# coolaz-sheet.net
KiCad netlist of a schematic drawn in Altium Designer
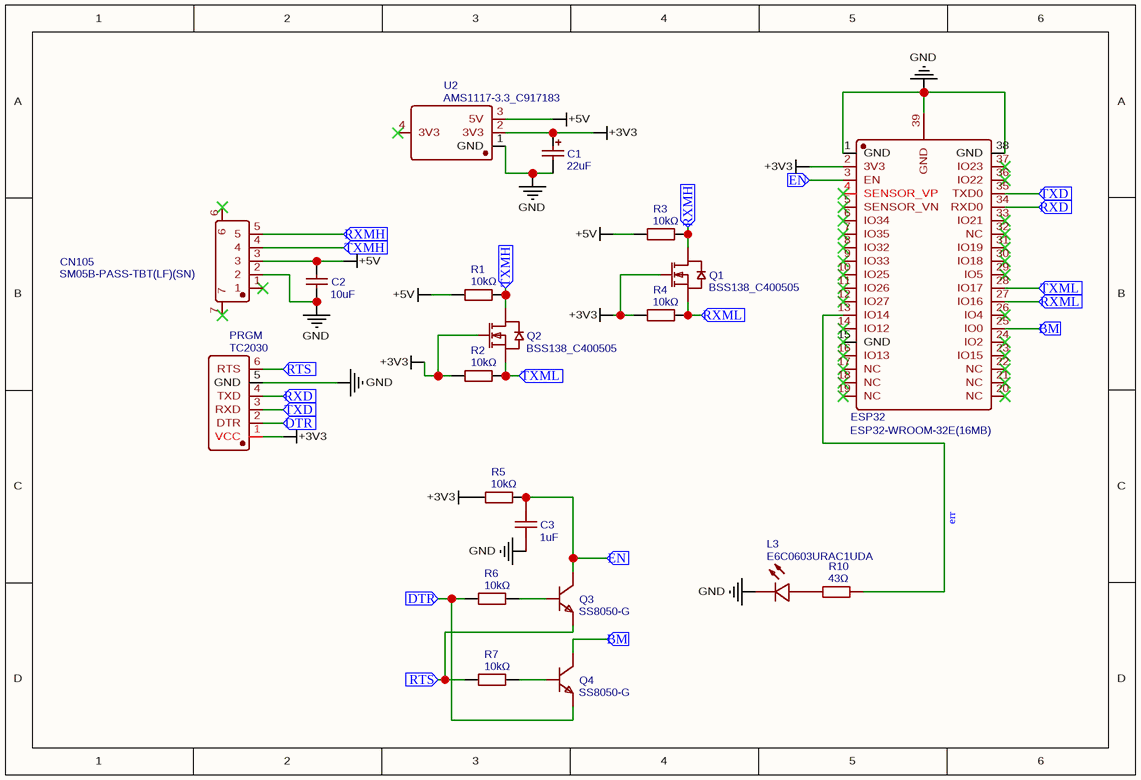
[diagram p0: coolaz-sheet.schdoc]

(export (version "E")
  (design (tool "Eeschema 10.0.6"))
  (components
    (comp (ref "C1")
      (value "22uF")
      (fields
        (field (name "BOM_MANUFACTURER PART") "CA45-B-16V-22UF-K")
        (field (name "BOM_SUPPLIER PART") "C129568")
      )
      (libsource (lib "altium-import") (part "root_1_22uF_"))
    )
    (comp (ref "C2")
      (value "10uF")
      (fields
        (field (name "BOM_MANUFACTURER PART") "CL05A106MQ5NUNC")
        (field (name "BOM_SUPPLIER PART") "C15525")
      )
      (libsource (lib "altium-import") (part "root_1_10uF_"))
    )
    (comp (ref "C3")
      (value "1uF")
      (fields
        (field (name "BOM_MANUFACTURER PART") "CL05A105KA5NQNC")
        (field (name "BOM_SUPPLIER PART") "C52923")
      )
      (libsource (lib "altium-import") (part "root_1_1uF_"))
    )
    (comp (ref "CN105")
      (value "SM05B-PASS-TBT(LF)(SN)")
      (fields (field (name "BOM_SUPPLIER PART") "C485350") (field (name "CONTRIBUTOR") "LCSC"))
      (libsource (lib "altium-import") (part "root_2_SM05B-PASS-TBT(LF)(SN)_"))
    )
    (comp (ref "ESP32")
      (value "ESP32-WROOM-32E(16MB)")
      (fields (field (name "BOM_SUPPLIER PART") "C701343") (field (name "CONTRIBUTOR") "LCSC"))
      (libsource (lib "altium-import") (part "root_0_ESP32-WROOM-32E(16MB)_"))
    )
    (comp (ref "L3")
      (value "E6C0603URAC1UDA")
      (fields (field (name "BOM_SUPPLIER PART") "C375444") (field (name "CONTRIBUTOR") "LCSC"))
      (libsource (lib "altium-import") (part "root_0_E6C0603URAC1UDA_"))
    )
    (comp (ref "PRGM")
      (value "TC2030")
      (fields
        (field (name "BOM_MANUFACTURER PART") "TC2030-FTDI-C232HD-DDHSP-0-DTR")
        (field (name "CONTRIBUTOR") "thomas_1863")
      )
      (libsource (lib "altium-import") (part "root_2_TC2030_"))
    )
    (comp (ref "Q1")
      (value "BSS138_C400505")
      (fields
        (field (name "BOM_SUPPLIER PART") "C400505")
        (field (name "BOM_MANUFACTURER PART") "BSS138")
        (field (name "CONTRIBUTOR") "LCSC")
      )
      (libsource (lib "altium-import") (part "root_0_BSS138_C400505_"))
    )
    (comp (ref "Q2")
      (value "BSS138_C400505")
      (fields
        (field (name "BOM_SUPPLIER PART") "C400505")
        (field (name "BOM_MANUFACTURER PART") "BSS138")
        (field (name "CONTRIBUTOR") "LCSC")
      )
      (libsource (lib "altium-import") (part "root_0_BSS138_C400505_"))
    )
    (comp (ref "Q3")
      (value "SS8050-G")
      (fields (field (name "BOM_SUPPLIER PART") "C164886") (field (name "CONTRIBUTOR") "LCSC"))
      (libsource (lib "altium-import") (part "root_0_SS8050-G_"))
    )
    (comp (ref "Q4")
      (value "SS8050-G")
      (fields (field (name "BOM_SUPPLIER PART") "C164886") (field (name "CONTRIBUTOR") "LCSC"))
      (libsource (lib "altium-import") (part "root_0_SS8050-G_"))
    )
    (comp (ref "R1")
      (value "10kΩ")
      (fields
        (field (name "BOM_MANUFACTURER PART") "0603WAF1002T5E")
        (field (name "BOM_SUPPLIER PART") "C25804")
      )
      (libsource (lib "altium-import") (part "root_0_10kΩ_"))
    )
    (comp (ref "R2")
      (value "10kΩ")
      (fields
        (field (name "BOM_MANUFACTURER PART") "0603WAF1002T5E")
        (field (name "BOM_SUPPLIER PART") "C25804")
      )
      (libsource (lib "altium-import") (part "root_0_10kΩ_"))
    )
    (comp (ref "R3")
      (value "10kΩ")
      (fields
        (field (name "BOM_MANUFACTURER PART") "0603WAF1002T5E")
        (field (name "BOM_SUPPLIER PART") "C25804")
      )
      (libsource (lib "altium-import") (part "root_0_10kΩ_"))
    )
    (comp (ref "R4")
      (value "10kΩ")
      (fields
        (field (name "BOM_MANUFACTURER PART") "0603WAF1002T5E")
        (field (name "BOM_SUPPLIER PART") "C25804")
      )
      (libsource (lib "altium-import") (part "root_0_10kΩ_"))
    )
    (comp (ref "R5")
      (value "10kΩ")
      (fields
        (field (name "BOM_MANUFACTURER PART") "0603WAF1002T5E")
        (field (name "BOM_SUPPLIER PART") "C25804")
      )
      (libsource (lib "altium-import") (part "root_0_10kΩ_"))
    )
    (comp (ref "R6")
      (value "10kΩ")
      (fields
        (field (name "BOM_MANUFACTURER PART") "0603WAF1002T5E")
        (field (name "BOM_SUPPLIER PART") "C25804")
      )
      (libsource (lib "altium-import") (part "root_0_10kΩ_"))
    )
    (comp (ref "R7")
      (value "10kΩ")
      (fields
        (field (name "BOM_MANUFACTURER PART") "0603WAF1002T5E")
        (field (name "BOM_SUPPLIER PART") "C25804")
      )
      (libsource (lib "altium-import") (part "root_0_10kΩ_"))
    )
    (comp (ref "R10")
      (value "43Ω")
      (fields
        (field (name "BOM_SUPPLIER PART") "C270600")
        (field (name "BOM_MANUFACTURER PART") "0402WGF430JTCE")
        (field (name "CONTRIBUTOR") "LCSC")
      )
      (libsource (lib "altium-import") (part "root_0_43Ω_"))
    )
    (comp (ref "U2")
      (value "AMS1117-3.3_C917183")
      (fields
        (field (name "BOM_SUPPLIER PART") "C917183")
        (field (name "BOM_MANUFACTURER PART") "AMS1117-3.3")
        (field (name "CONTRIBUTOR") "LCSC")
      )
      (libsource (lib "altium-import") (part "root_2_AMS1117-3.3_C917183_"))
    )
  )
  (nets
    (net (code "1") (name "+3V3") (class "Default")
      (node (ref "C1") (pin "1") (pinfunction "1_1") (pintype "passive"))
      (node (ref "ESP32") (pin "2") (pinfunction "3V3_2") (pintype "passive"))
      (node (ref "PRGM") (pin "1") (pinfunction "VCC_1") (pintype "passive"))
      (node (ref "Q1") (pin "1") (pinfunction "G_1") (pintype "passive"))
      (node (ref "Q2") (pin "1") (pinfunction "G_1") (pintype "passive"))
      (node (ref "R2") (pin "1") (pinfunction "1_1") (pintype "passive"))
      (node (ref "R4") (pin "1") (pinfunction "1_1") (pintype "passive"))
      (node (ref "R5") (pin "1") (pinfunction "1_1") (pintype "passive"))
      (node (ref "U2") (pin "2") (pinfunction "3V3_2") (pintype "passive"))
    )
    (net (code "2") (name "+5V") (class "Default")
      (node (ref "C2") (pin "2") (pinfunction "2_2") (pintype "passive"))
      (node (ref "CN105") (pin "3") (pinfunction "3_3") (pintype "passive"))
      (node (ref "R1") (pin "1") (pinfunction "1_1") (pintype "passive"))
      (node (ref "R3") (pin "1") (pinfunction "1_1") (pintype "passive"))
      (node (ref "U2") (pin "3") (pinfunction "5V_3") (pintype "passive"))
    )
    (net (code "3") (name "/BM") (class "Default")
      (node (ref "ESP32") (pin "25") (pinfunction "IO0_25") (pintype "passive"))
      (node (ref "Q4") (pin "3") (pinfunction "C_3") (pintype "passive"))
    )
    (net (code "4") (name "/DTR") (class "Default")
      (node (ref "PRGM") (pin "2") (pinfunction "DTR_2") (pintype "passive"))
      (node (ref "Q4") (pin "2") (pinfunction "E_2") (pintype "passive"))
      (node (ref "R6") (pin "1") (pinfunction "1_1") (pintype "passive"))
    )
    (net (code "5") (name "/EN") (class "Default")
      (node (ref "C3") (pin "2") (pinfunction "2_2") (pintype "passive"))
      (node (ref "ESP32") (pin "3") (pinfunction "EN_3") (pintype "passive"))
      (node (ref "Q3") (pin "3") (pinfunction "C_3") (pintype "passive"))
      (node (ref "R5") (pin "2") (pinfunction "2_2") (pintype "passive"))
    )
    (net (code "6") (name "/RTS") (class "Default")
      (node (ref "PRGM") (pin "6") (pinfunction "RTS_6") (pintype "passive"))
      (node (ref "Q3") (pin "2") (pinfunction "E_2") (pintype "passive"))
      (node (ref "R7") (pin "1") (pinfunction "1_1") (pintype "passive"))
    )
    (net (code "7") (name "/RXD") (class "Default")
      (node (ref "ESP32") (pin "34") (pinfunction "RXD0_34") (pintype "passive"))
      (node (ref "PRGM") (pin "4") (pinfunction "TXD_4") (pintype "passive"))
    )
    (net (code "8") (name "/RXMH") (class "Default")
      (node (ref "CN105") (pin "5") (pinfunction "5_5") (pintype "passive"))
      (node (ref "Q1") (pin "3") (pinfunction "D_3") (pintype "passive"))
      (node (ref "R3") (pin "2") (pinfunction "2_2") (pintype "passive"))
    )
    (net (code "9") (name "/RXML") (class "Default")
      (node (ref "ESP32") (pin "27") (pinfunction "IO16_27") (pintype "passive"))
      (node (ref "Q1") (pin "2") (pinfunction "S_2") (pintype "passive"))
      (node (ref "R4") (pin "2") (pinfunction "2_2") (pintype "passive"))
    )
    (net (code "10") (name "/TXD") (class "Default")
      (node (ref "ESP32") (pin "35") (pinfunction "TXD0_35") (pintype "passive"))
      (node (ref "PRGM") (pin "3") (pinfunction "RXD_3") (pintype "passive"))
    )
    (net (code "11") (name "/TXMH") (class "Default")
      (node (ref "CN105") (pin "4") (pinfunction "4_4") (pintype "passive"))
      (node (ref "Q2") (pin "3") (pinfunction "D_3") (pintype "passive"))
      (node (ref "R1") (pin "2") (pinfunction "2_2") (pintype "passive"))
    )
    (net (code "12") (name "/TXML") (class "Default")
      (node (ref "ESP32") (pin "28") (pinfunction "IO17_28") (pintype "passive"))
      (node (ref "Q2") (pin "2") (pinfunction "S_2") (pintype "passive"))
      (node (ref "R2") (pin "2") (pinfunction "2_2") (pintype "passive"))
    )
    (net (code "13") (name "/err") (class "Default")
      (node (ref "ESP32") (pin "13") (pinfunction "IO14_13") (pintype "passive"))
      (node (ref "R10") (pin "2") (pinfunction "2_2") (pintype "passive"))
    )
    (net (code "14") (name "GND") (class "Default")
      (node (ref "C1") (pin "2") (pinfunction "2_2") (pintype "passive"))
      (node (ref "C2") (pin "1") (pinfunction "1_1") (pintype "passive"))
      (node (ref "C3") (pin "1") (pinfunction "1_1") (pintype "passive"))
      (node (ref "CN105") (pin "2") (pinfunction "2_2") (pintype "passive"))
      (node (ref "ESP32") (pin "1") (pinfunction "GND_1") (pintype "passive"))
      (node (ref "ESP32") (pin "38") (pinfunction "GND_38") (pintype "passive"))
      (node (ref "ESP32") (pin "39") (pinfunction "GND_39") (pintype "passive"))
      (node (ref "L3") (pin "2") (pinfunction "-_2") (pintype "passive"))
      (node (ref "PRGM") (pin "5") (pinfunction "GND_5") (pintype "passive"))
      (node (ref "U2") (pin "1") (pinfunction "GND_1") (pintype "passive"))
    )
    (net (code "15") (name "Net-(L3-+)") (class "Default")
      (node (ref "L3") (pin "1") (pinfunction "+_1") (pintype "passive"))
      (node (ref "R10") (pin "1") (pinfunction "1_1") (pintype "passive"))
    )
    (net (code "16") (name "Net-(Q3-B)") (class "Default")
      (node (ref "Q3") (pin "1") (pinfunction "B_1") (pintype "passive"))
      (node (ref "R6") (pin "2") (pinfunction "2_2") (pintype "passive"))
    )
    (net (code "17") (name "Net-(Q4-B)") (class "Default")
      (node (ref "Q4") (pin "1") (pinfunction "B_1") (pintype "passive"))
      (node (ref "R7") (pin "2") (pinfunction "2_2") (pintype "passive"))
    )
    (net (code "18") (name "unconnected-(CN105-Pad1)") (class "Default")
      (node (ref "CN105") (pin "1") (pinfunction "1_1") (pintype "passive+no_connect"))
    )
    (net (code "19") (name "unconnected-(CN105-Pad6)") (class "Default")
      (node (ref "CN105") (pin "6") (pinfunction "6_6") (pintype "passive+no_connect"))
    )
    (net (code "20") (name "unconnected-(CN105-Pad7)") (class "Default")
      (node (ref "CN105") (pin "7") (pinfunction "7_7") (pintype "passive+no_connect"))
    )
    (net (code "21") (name "unconnected-(ESP32-GND-Pad15)") (class "Default")
      (node (ref "ESP32") (pin "15") (pinfunction "GND_15") (pintype "passive+no_connect"))
    )
    (net (code "22") (name "unconnected-(ESP32-IO2-Pad24)") (class "Default")
      (node (ref "ESP32") (pin "24") (pinfunction "IO2_24") (pintype "passive+no_connect"))
    )
    (net (code "23") (name "unconnected-(ESP32-IO4-Pad26)") (class "Default")
      (node (ref "ESP32") (pin "26") (pinfunction "IO4_26") (pintype "passive+no_connect"))
    )
    (net (code "24") (name "unconnected-(ESP32-IO5-Pad29)") (class "Default")
      (node (ref "ESP32") (pin "29") (pinfunction "IO5_29") (pintype "passive+no_connect"))
    )
    (net (code "25") (name "unconnected-(ESP32-IO12-Pad14)") (class "Default")
      (node (ref "ESP32") (pin "14") (pinfunction "IO12_14") (pintype "passive+no_connect"))
    )
    (net (code "26") (name "unconnected-(ESP32-IO13-Pad16)") (class "Default")
      (node (ref "ESP32") (pin "16") (pinfunction "IO13_16") (pintype "passive+no_connect"))
    )
    (net (code "27") (name "unconnected-(ESP32-IO15-Pad23)") (class "Default")
      (node (ref "ESP32") (pin "23") (pinfunction "IO15_23") (pintype "passive+no_connect"))
    )
    (net (code "28") (name "unconnected-(ESP32-IO18-Pad30)") (class "Default")
      (node (ref "ESP32") (pin "30") (pinfunction "IO18_30") (pintype "passive+no_connect"))
    )
    (net (code "29") (name "unconnected-(ESP32-IO19-Pad31)") (class "Default")
      (node (ref "ESP32") (pin "31") (pinfunction "IO19_31") (pintype "passive+no_connect"))
    )
    (net (code "30") (name "unconnected-(ESP32-IO21-Pad33)") (class "Default")
      (node (ref "ESP32") (pin "33") (pinfunction "IO21_33") (pintype "passive+no_connect"))
    )
    (net (code "31") (name "unconnected-(ESP32-IO22-Pad36)") (class "Default")
      (node (ref "ESP32") (pin "36") (pinfunction "IO22_36") (pintype "passive+no_connect"))
    )
    (net (code "32") (name "unconnected-(ESP32-IO23-Pad37)") (class "Default")
      (node (ref "ESP32") (pin "37") (pinfunction "IO23_37") (pintype "passive+no_connect"))
    )
    (net (code "33") (name "unconnected-(ESP32-IO25-Pad10)") (class "Default")
      (node (ref "ESP32") (pin "10") (pinfunction "IO25_10") (pintype "passive+no_connect"))
    )
    (net (code "34") (name "unconnected-(ESP32-IO26-Pad11)") (class "Default")
      (node (ref "ESP32") (pin "11") (pinfunction "IO26_11") (pintype "passive+no_connect"))
    )
    (net (code "35") (name "unconnected-(ESP32-IO27-Pad12)") (class "Default")
      (node (ref "ESP32") (pin "12") (pinfunction "IO27_12") (pintype "passive+no_connect"))
    )
    (net (code "36") (name "unconnected-(ESP32-IO32-Pad8)") (class "Default")
      (node (ref "ESP32") (pin "8") (pinfunction "IO32_8") (pintype "passive+no_connect"))
    )
    (net (code "37") (name "unconnected-(ESP32-IO33-Pad9)") (class "Default")
      (node (ref "ESP32") (pin "9") (pinfunction "IO33_9") (pintype "passive+no_connect"))
    )
    (net (code "38") (name "unconnected-(ESP32-IO34-Pad6)") (class "Default")
      (node (ref "ESP32") (pin "6") (pinfunction "IO34_6") (pintype "passive+no_connect"))
    )
    (net (code "39") (name "unconnected-(ESP32-IO35-Pad7)") (class "Default")
      (node (ref "ESP32") (pin "7") (pinfunction "IO35_7") (pintype "passive+no_connect"))
    )
    (net (code "40") (name "unconnected-(ESP32-NC-Pad17)") (class "Default")
      (node (ref "ESP32") (pin "17") (pinfunction "NC_17") (pintype "passive+no_connect"))
    )
    (net (code "41") (name "unconnected-(ESP32-NC-Pad18)") (class "Default")
      (node (ref "ESP32") (pin "18") (pinfunction "NC_18") (pintype "passive+no_connect"))
    )
    (net (code "42") (name "unconnected-(ESP32-NC-Pad19)") (class "Default")
      (node (ref "ESP32") (pin "19") (pinfunction "NC_19") (pintype "passive+no_connect"))
    )
    (net (code "43") (name "unconnected-(ESP32-NC-Pad20)") (class "Default")
      (node (ref "ESP32") (pin "20") (pinfunction "NC_20") (pintype "passive+no_connect"))
    )
    (net (code "44") (name "unconnected-(ESP32-NC-Pad21)") (class "Default")
      (node (ref "ESP32") (pin "21") (pinfunction "NC_21") (pintype "passive+no_connect"))
    )
    (net (code "45") (name "unconnected-(ESP32-NC-Pad22)") (class "Default")
      (node (ref "ESP32") (pin "22") (pinfunction "NC_22") (pintype "passive+no_connect"))
    )
    (net (code "46") (name "unconnected-(ESP32-NC-Pad32)") (class "Default")
      (node (ref "ESP32") (pin "32") (pinfunction "NC_32") (pintype "passive+no_connect"))
    )
    (net (code "47") (name "unconnected-(ESP32-SENSOR_VN-Pad5)") (class "Default")
      (node (ref "ESP32") (pin "5") (pinfunction "SENSOR_VN_5") (pintype "passive+no_connect"))
    )
    (net (code "48") (name "unconnected-(ESP32-SENSOR_VP-Pad4)") (class "Default")
      (node (ref "ESP32") (pin "4") (pinfunction "SENSOR_VP_4") (pintype "passive+no_connect"))
    )
    (net (code "49") (name "unconnected-(U2-3V3-Pad4)") (class "Default")
      (node (ref "U2") (pin "4") (pinfunction "3V3_4") (pintype "passive+no_connect"))
    )
  )
)
